# A.net
KiCad netlist of a schematic drawn in Altium Designer
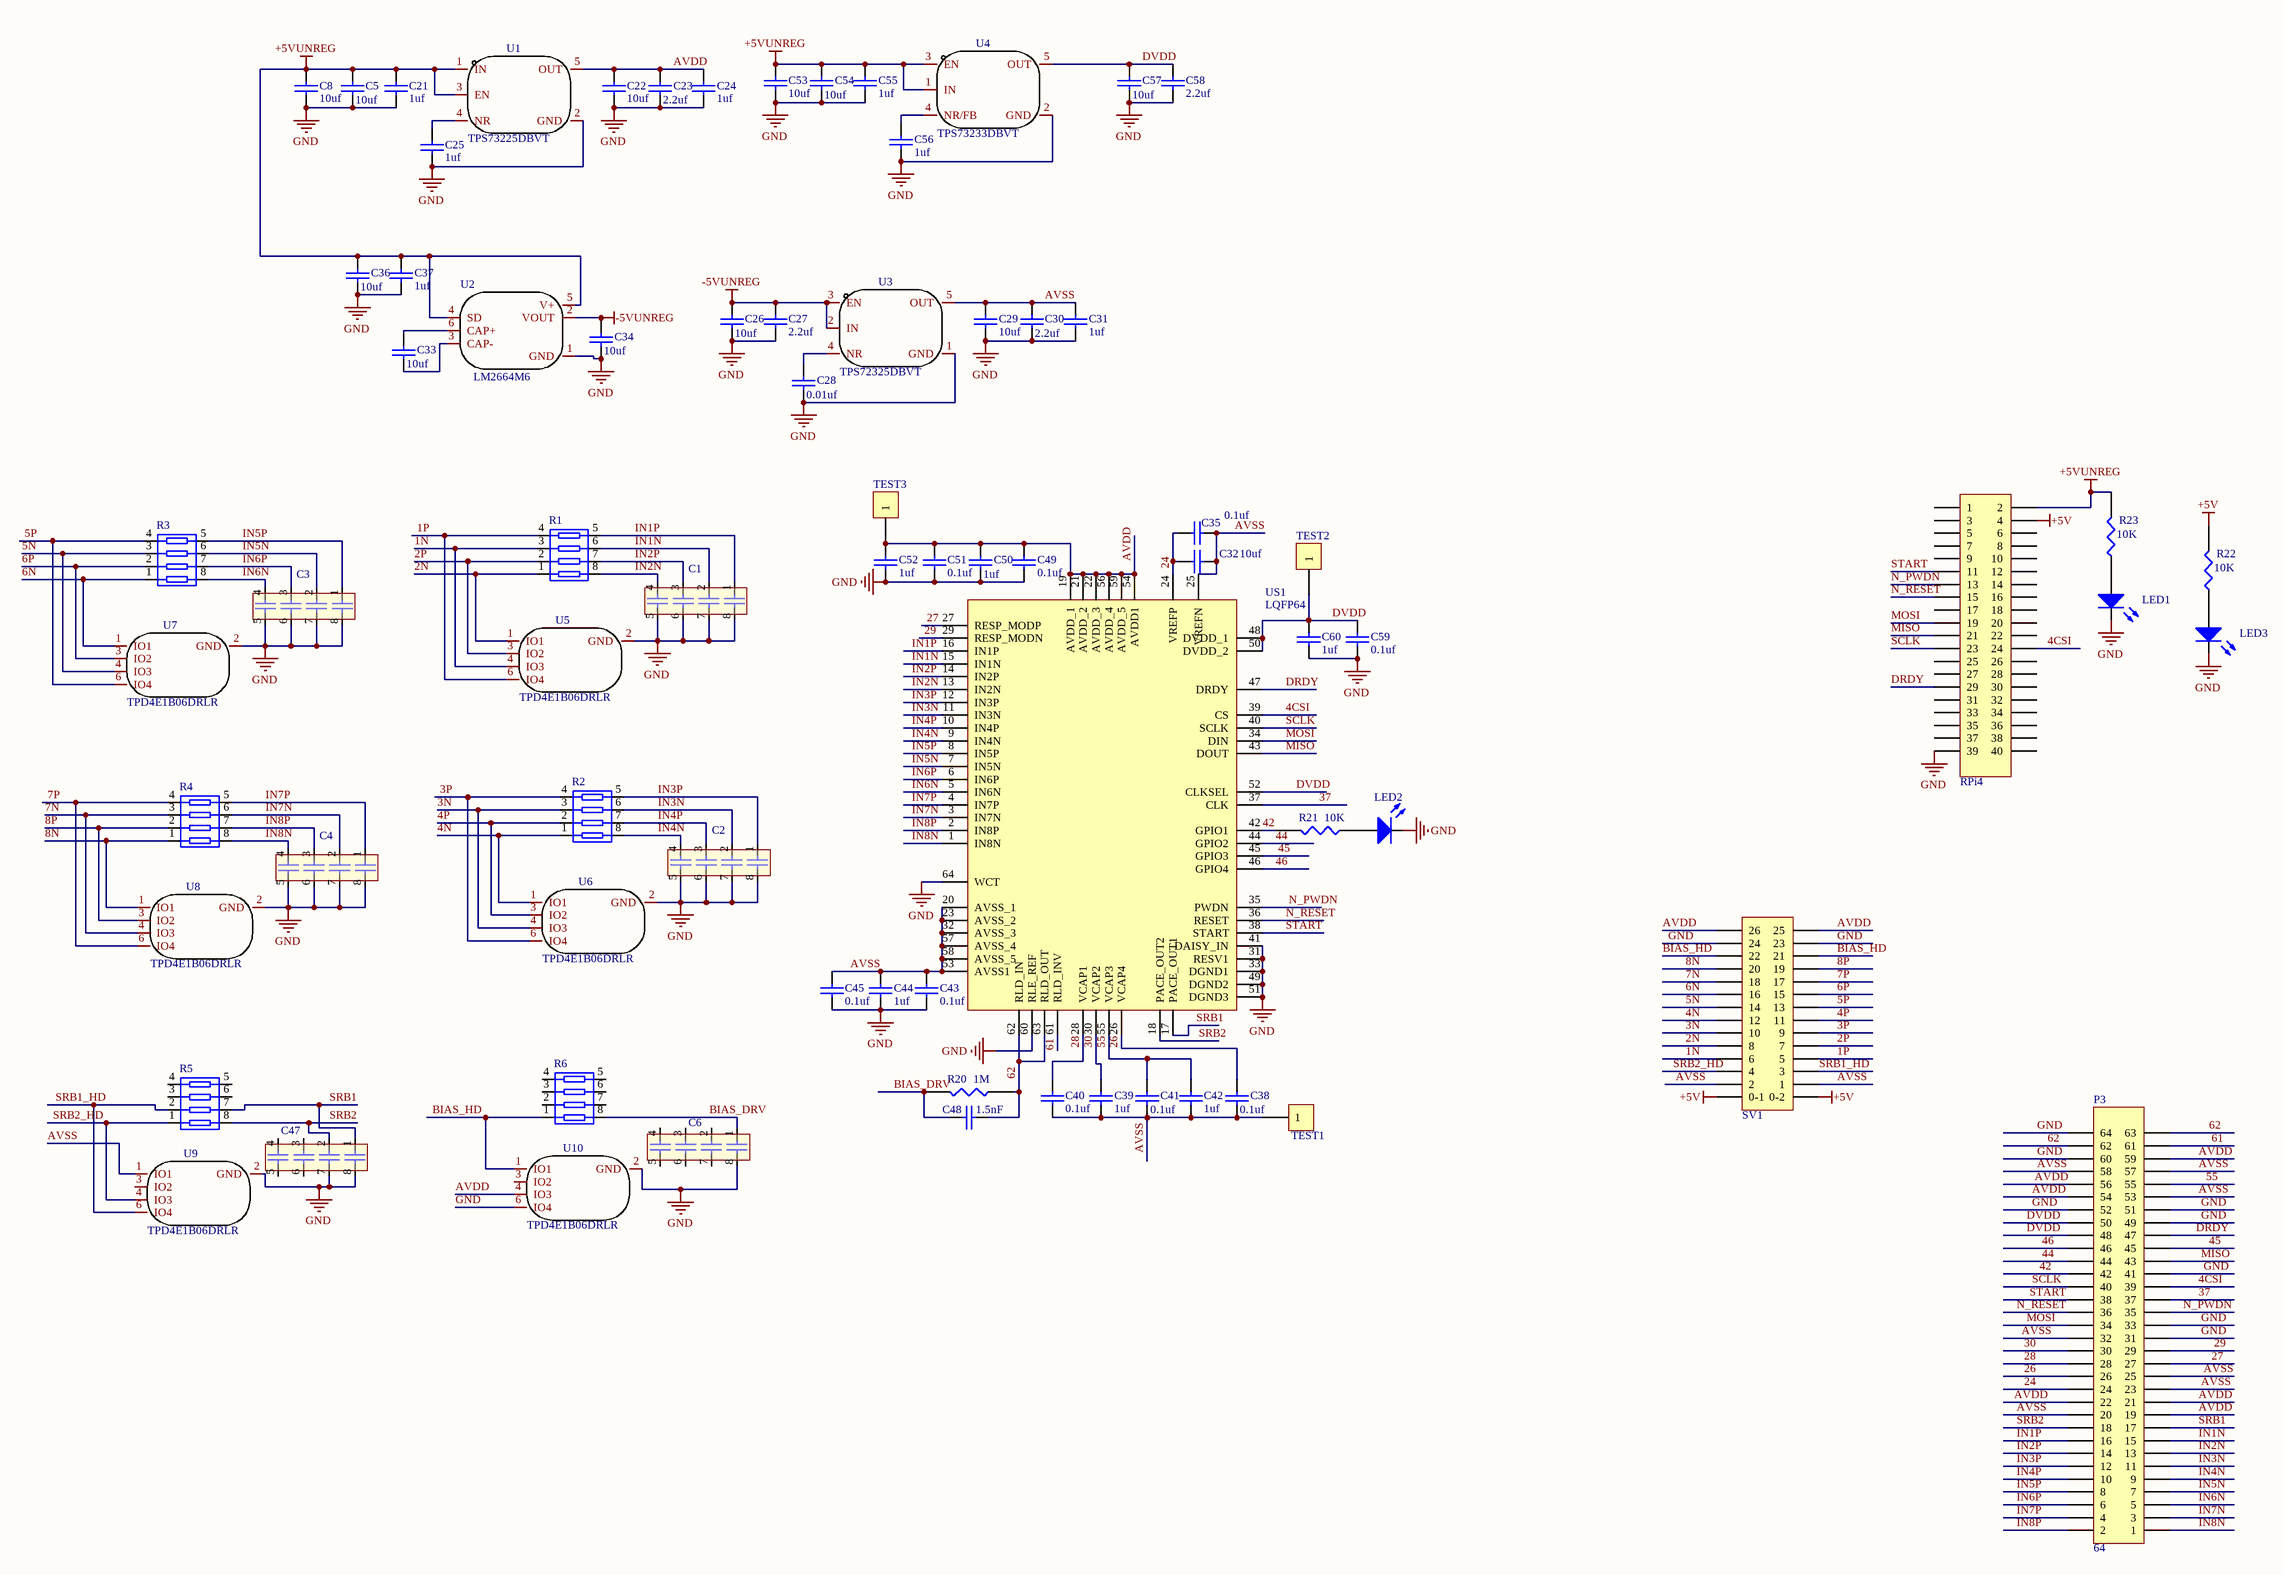
[diagram p0: A.SchDoc]

(export (version "E")
  (design (tool "Eeschema 10.0.6"))
  (components
    (comp (ref "C1") (value "~") (footprint "0805 array") (libsource (lib "") (part "8P4R_1")))
    (comp (ref "C2") (value "~") (footprint "0805 array") (libsource (lib "") (part "8P4R_1")))
    (comp (ref "C3") (value "~") (footprint "0805 array") (libsource (lib "") (part "8P4R_1")))
    (comp (ref "C4") (value "~") (footprint "0805 array") (libsource (lib "") (part "8P4R_1")))
    (comp (ref "C5")
      (value "10uf")
      (footprint "0805")
      (description "Capacitor")
      (libsource (lib "*") (part "CAP"))
    )
    (comp (ref "C6") (value "~") (footprint "0805 array") (libsource (lib "") (part "8P4R_1")))
    (comp (ref "C8")
      (value "10uf")
      (footprint "0805")
      (description "Capacitor")
      (libsource (lib "*") (part "CAP"))
    )
    (comp (ref "C21")
      (value "1uf")
      (footprint "0805")
      (description "Capacitor")
      (libsource (lib "*") (part "CAP"))
    )
    (comp (ref "C22")
      (value "10uf")
      (footprint "0805")
      (description "Capacitor")
      (libsource (lib "*") (part "CAP"))
    )
    (comp (ref "C23")
      (value "2.2uf")
      (footprint "0805")
      (description "Capacitor")
      (libsource (lib "*") (part "CAP"))
    )
    (comp (ref "C24")
      (value "1uf")
      (footprint "0805")
      (description "Capacitor")
      (libsource (lib "*") (part "CAP"))
    )
    (comp (ref "C25")
      (value "1uf")
      (footprint "0805")
      (description "Capacitor")
      (libsource (lib "*") (part "CAP"))
    )
    (comp (ref "C26")
      (value "10uf")
      (footprint "0805")
      (description "Capacitor")
      (libsource (lib "*") (part "CAP"))
    )
    (comp (ref "C27")
      (value "2.2uf")
      (footprint "0805")
      (description "Capacitor")
      (libsource (lib "*") (part "CAP"))
    )
    (comp (ref "C28")
      (value "0.01uf")
      (footprint "0805")
      (description "Capacitor")
      (libsource (lib "*") (part "CAP"))
    )
    (comp (ref "C29")
      (value "10uf")
      (footprint "0805")
      (description "Capacitor")
      (libsource (lib "*") (part "CAP"))
    )
    (comp (ref "C30")
      (value "2.2uf")
      (footprint "0805")
      (description "Capacitor")
      (libsource (lib "*") (part "CAP"))
    )
    (comp (ref "C31")
      (value "1uf")
      (footprint "0805")
      (description "Capacitor")
      (libsource (lib "*") (part "CAP"))
    )
    (comp (ref "C32")
      (value "10uf")
      (footprint "0805")
      (description "Capacitor")
      (libsource (lib "*") (part "CAP"))
    )
    (comp (ref "C33")
      (value "10uf")
      (footprint "0805")
      (description "Capacitor")
      (libsource (lib "*") (part "CAP"))
    )
    (comp (ref "C34")
      (value "10uf")
      (footprint "0805")
      (description "Capacitor")
      (libsource (lib "*") (part "CAP"))
    )
    (comp (ref "C35")
      (value "0.1uf")
      (footprint "0805")
      (description "Capacitor")
      (libsource (lib "*") (part "CAP"))
    )
    (comp (ref "C36")
      (value "10uf")
      (footprint "0805")
      (description "Capacitor")
      (libsource (lib "*") (part "CAP"))
    )
    (comp (ref "C37")
      (value "1uf")
      (footprint "0805")
      (description "Capacitor")
      (libsource (lib "*") (part "CAP"))
    )
    (comp (ref "C38")
      (value "0.1uf")
      (footprint "0805")
      (description "Capacitor")
      (libsource (lib "*") (part "CAP"))
    )
    (comp (ref "C39")
      (value "1uf")
      (footprint "0805")
      (description "Capacitor")
      (libsource (lib "*") (part "CAP"))
    )
    (comp (ref "C40")
      (value "0.1uf")
      (footprint "0805")
      (description "Capacitor")
      (libsource (lib "*") (part "CAP"))
    )
    (comp (ref "C41")
      (value "0.1uf")
      (footprint "0805")
      (description "Capacitor")
      (libsource (lib "*") (part "CAP"))
    )
    (comp (ref "C42")
      (value "1uf")
      (footprint "0805")
      (description "Capacitor")
      (libsource (lib "*") (part "CAP"))
    )
    (comp (ref "C43")
      (value "0.1uf")
      (footprint "0805")
      (description "Capacitor")
      (libsource (lib "*") (part "CAP"))
    )
    (comp (ref "C44")
      (value "1uf")
      (footprint "0805")
      (description "Capacitor")
      (libsource (lib "*") (part "CAP"))
    )
    (comp (ref "C45")
      (value "0.1uf")
      (footprint "0805")
      (description "Capacitor")
      (libsource (lib "*") (part "CAP"))
    )
    (comp (ref "C47") (value "~") (footprint "0805 array") (libsource (lib "") (part "8P4R_1")))
    (comp (ref "C48")
      (value "1.5nF")
      (footprint "0805")
      (description "Capacitor")
      (libsource (lib "*") (part "CAP"))
    )
    (comp (ref "C49")
      (value "0.1uf")
      (footprint "0805")
      (description "Capacitor")
      (libsource (lib "*") (part "CAP"))
    )
    (comp (ref "C50")
      (value "1uf")
      (footprint "0805")
      (description "Capacitor")
      (libsource (lib "*") (part "CAP"))
    )
    (comp (ref "C51")
      (value "0.1uf")
      (footprint "0805")
      (description "Capacitor")
      (libsource (lib "*") (part "CAP"))
    )
    (comp (ref "C52")
      (value "1uf")
      (footprint "0805")
      (description "Capacitor")
      (libsource (lib "*") (part "CAP"))
    )
    (comp (ref "C53")
      (value "10uf")
      (footprint "0805")
      (description "Capacitor")
      (libsource (lib "*") (part "CAP"))
    )
    (comp (ref "C54")
      (value "10uf")
      (footprint "0805")
      (description "Capacitor")
      (libsource (lib "*") (part "CAP"))
    )
    (comp (ref "C55")
      (value "1uf")
      (footprint "0805")
      (description "Capacitor")
      (libsource (lib "*") (part "CAP"))
    )
    (comp (ref "C56")
      (value "1uf")
      (footprint "0805")
      (description "Capacitor")
      (libsource (lib "*") (part "CAP"))
    )
    (comp (ref "C57")
      (value "10uf")
      (footprint "0805")
      (description "Capacitor")
      (libsource (lib "*") (part "CAP"))
    )
    (comp (ref "C58")
      (value "2.2uf")
      (footprint "0805")
      (description "Capacitor")
      (libsource (lib "*") (part "CAP"))
    )
    (comp (ref "C59")
      (value "0.1uf")
      (footprint "0805")
      (description "Capacitor")
      (libsource (lib "*") (part "CAP"))
    )
    (comp (ref "C60")
      (value "1uf")
      (footprint "0805")
      (description "Capacitor")
      (libsource (lib "*") (part "CAP"))
    )
    (comp (ref "LED1") (value "~") (footprint "0805") (libsource (lib "schematic library") (part "LED")))
    (comp (ref "LED2") (value "~") (footprint "0805") (libsource (lib "schematic library") (part "LED")))
    (comp (ref "LED3") (value "~") (footprint "0805") (libsource (lib "schematic library") (part "LED")))
    (comp (ref "P3") (value "64") (footprint "64") (libsource (lib "1299") (part "64")))
    (comp (ref "R1") (value "~") (footprint "8P4R") (libsource (lib "schematic library") (part "8P4R")))
    (comp (ref "R2") (value "~") (footprint "8P4R") (libsource (lib "schematic library") (part "8P4R")))
    (comp (ref "R3") (value "~") (footprint "8P4R") (libsource (lib "schematic library") (part "8P4R")))
    (comp (ref "R4") (value "~") (footprint "8P4R") (libsource (lib "schematic library") (part "8P4R")))
    (comp (ref "R5") (value "~") (footprint "8P4R") (libsource (lib "schematic library") (part "8P4R")))
    (comp (ref "R6") (value "~") (footprint "8P4R") (libsource (lib "schematic library") (part "8P4R")))
    (comp (ref "R20") (value "1M") (footprint "0805") (libsource (lib "*") (part "RES1")))
    (comp (ref "R21") (value "10K") (footprint "0805") (libsource (lib "*") (part "RES1")))
    (comp (ref "R22") (value "10K") (footprint "0805") (libsource (lib "*") (part "RES1")))
    (comp (ref "R23") (value "10K") (footprint "0805") (libsource (lib "*") (part "RES1")))
    (comp (ref "RPi4") (value "RP13") (footprint "40") (libsource (lib "1299") (part "40")))
    (comp (ref "SV1") (value "SV1") (footprint "26") (libsource (lib "A") (part "26")))
    (comp (ref "TEST1")
      (value "TEST2")
      (footprint "P")
      (description "Connector")
      (libsource (lib "") (part "CON1_1"))
    )
    (comp (ref "TEST2")
      (value "TEST3")
      (footprint "P")
      (description "Connector")
      (libsource (lib "*") (part "CON1"))
    )
    (comp (ref "TEST3")
      (value "TEST4")
      (footprint "P")
      (description "Connector")
      (libsource (lib "*") (part "CON1"))
    )
    (comp (ref "U1") (value "TPS73225DBVT") (footprint "sot23-5") (libsource (lib "1299") (part "5")))
    (comp (ref "U2") (value "LM2664M6") (footprint "sot23-6") (libsource (lib "1299") (part "6")))
    (comp (ref "U3") (value "TPS72325DBVT") (footprint "sot23-5") (libsource (lib "") (part "5_2")))
    (comp (ref "U4") (value "TPS73233DBVT") (footprint "sot23-5") (libsource (lib "") (part "5_1")))
    (comp (ref "U5") (value "TPD4E1B06DRLR") (footprint "sot563") (libsource (lib "1299") (part "6+")))
    (comp (ref "U6") (value "TPD4E1B06DRLR") (footprint "sot563") (libsource (lib "1299") (part "6+")))
    (comp (ref "U7") (value "TPD4E1B06DRLR") (footprint "sot563") (libsource (lib "1299") (part "6+")))
    (comp (ref "U8") (value "TPD4E1B06DRLR") (footprint "sot563") (libsource (lib "1299") (part "6+")))
    (comp (ref "U9") (value "TPD4E1B06DRLR") (footprint "sot563") (libsource (lib "1299") (part "6+")))
    (comp (ref "U10") (value "TPD4E1B06DRLR") (footprint "sot563") (libsource (lib "1299") (part "6+")))
    (comp (ref "US1") (value "LQFP64") (footprint "TQFP64") (libsource (lib "1299") (part "LQFP64")))
  )
  (nets
    (net (code "1") (name "+5V") (class "Default")
      (node (ref "R22") (pin "2") (pinfunction "2_2") (pintype "passive"))
      (node (ref "RPi4") (pin "4") (pinfunction "4_4") (pintype "passive"))
      (node (ref "SV1") (pin "0-1") (pinfunction "0-1_0-1") (pintype "passive"))
      (node (ref "SV1") (pin "0-2") (pinfunction "0-2_0-2") (pintype "passive"))
    )
    (net (code "2") (name "+5VUNREG") (class "Default")
      (node (ref "C21") (pin "1") (pinfunction "1_1") (pintype "passive"))
      (node (ref "C36") (pin "1") (pinfunction "1_1") (pintype "passive"))
      (node (ref "C37") (pin "1") (pinfunction "1_1") (pintype "passive"))
      (node (ref "C5") (pin "1") (pinfunction "1_1") (pintype "passive"))
      (node (ref "C53") (pin "1") (pinfunction "1_1") (pintype "passive"))
      (node (ref "C54") (pin "1") (pinfunction "1_1") (pintype "passive"))
      (node (ref "C55") (pin "1") (pinfunction "1_1") (pintype "passive"))
      (node (ref "C8") (pin "1") (pinfunction "1_1") (pintype "passive"))
      (node (ref "R23") (pin "2") (pinfunction "2_2") (pintype "passive"))
      (node (ref "RPi4") (pin "2") (pinfunction "2_2") (pintype "passive"))
      (node (ref "U1") (pin "1") (pinfunction "IN_1") (pintype "passive"))
      (node (ref "U1") (pin "3") (pinfunction "EN_3") (pintype "passive"))
      (node (ref "U2") (pin "4") (pinfunction "SD_4") (pintype "passive"))
      (node (ref "U2") (pin "5") (pinfunction "V+_5") (pintype "passive"))
      (node (ref "U4") (pin "1") (pinfunction "IN_1") (pintype "passive"))
      (node (ref "U4") (pin "3") (pinfunction "EN_3") (pintype "passive"))
    )
    (net (code "3") (name "-5VUNREG") (class "Default")
      (node (ref "C26") (pin "1") (pinfunction "1_1") (pintype "passive"))
      (node (ref "C27") (pin "1") (pinfunction "1_1") (pintype "passive"))
      (node (ref "C34") (pin "1") (pinfunction "1_1") (pintype "passive"))
      (node (ref "U2") (pin "2") (pinfunction "VOUT_2") (pintype "passive"))
      (node (ref "U3") (pin "2") (pinfunction "IN_2") (pintype "passive"))
      (node (ref "U3") (pin "3") (pinfunction "EN_3") (pintype "passive"))
    )
    (net (code "4") (name "/1N") (class "Default")
      (node (ref "R1") (pin "3") (pinfunction "3_3") (pintype "passive"))
      (node (ref "SV1") (pin "6") (pinfunction "6_6") (pintype "passive"))
      (node (ref "U5") (pin "4") (pinfunction "IO3_4") (pintype "passive"))
    )
    (net (code "5") (name "/1P") (class "Default")
      (node (ref "R1") (pin "4") (pinfunction "4_4") (pintype "passive"))
      (node (ref "SV1") (pin "5") (pinfunction "5_5") (pintype "passive"))
      (node (ref "U5") (pin "6") (pinfunction "IO4_6") (pintype "passive"))
    )
    (net (code "6") (name "/2N") (class "Default")
      (node (ref "R1") (pin "1") (pinfunction "1_1") (pintype "passive"))
      (node (ref "SV1") (pin "8") (pinfunction "8_8") (pintype "passive"))
      (node (ref "U5") (pin "1") (pinfunction "IO1_1") (pintype "passive"))
    )
    (net (code "7") (name "/2P") (class "Default")
      (node (ref "R1") (pin "2") (pinfunction "2_2") (pintype "passive"))
      (node (ref "SV1") (pin "7") (pinfunction "7_7") (pintype "passive"))
      (node (ref "U5") (pin "3") (pinfunction "IO2_3") (pintype "passive"))
    )
    (net (code "8") (name "/3N") (class "Default")
      (node (ref "R2") (pin "3") (pinfunction "3_3") (pintype "passive"))
      (node (ref "SV1") (pin "10") (pinfunction "10_10") (pintype "passive"))
      (node (ref "U6") (pin "4") (pinfunction "IO3_4") (pintype "passive"))
    )
    (net (code "9") (name "/3P") (class "Default")
      (node (ref "R2") (pin "4") (pinfunction "4_4") (pintype "passive"))
      (node (ref "SV1") (pin "9") (pinfunction "9_9") (pintype "passive"))
      (node (ref "U6") (pin "6") (pinfunction "IO4_6") (pintype "passive"))
    )
    (net (code "10") (name "/4CSI") (class "Default")
      (node (ref "P3") (pin "39") (pinfunction "39_39") (pintype "passive"))
      (node (ref "RPi4") (pin "24") (pinfunction "24_24") (pintype "passive"))
      (node (ref "US1") (pin "39") (pinfunction "CS_39") (pintype "passive"))
    )
    (net (code "11") (name "/4N") (class "Default")
      (node (ref "R2") (pin "1") (pinfunction "1_1") (pintype "passive"))
      (node (ref "SV1") (pin "12") (pinfunction "12_12") (pintype "passive"))
      (node (ref "U6") (pin "1") (pinfunction "IO1_1") (pintype "passive"))
    )
    (net (code "12") (name "/4P") (class "Default")
      (node (ref "R2") (pin "2") (pinfunction "2_2") (pintype "passive"))
      (node (ref "SV1") (pin "11") (pinfunction "11_11") (pintype "passive"))
      (node (ref "U6") (pin "3") (pinfunction "IO2_3") (pintype "passive"))
    )
    (net (code "13") (name "/5N") (class "Default")
      (node (ref "R3") (pin "3") (pinfunction "3_3") (pintype "passive"))
      (node (ref "SV1") (pin "14") (pinfunction "14_14") (pintype "passive"))
      (node (ref "U7") (pin "4") (pinfunction "IO3_4") (pintype "passive"))
    )
    (net (code "14") (name "/5P") (class "Default")
      (node (ref "R3") (pin "4") (pinfunction "4_4") (pintype "passive"))
      (node (ref "SV1") (pin "13") (pinfunction "13_13") (pintype "passive"))
      (node (ref "U7") (pin "6") (pinfunction "IO4_6") (pintype "passive"))
    )
    (net (code "15") (name "/6N") (class "Default")
      (node (ref "R3") (pin "1") (pinfunction "1_1") (pintype "passive"))
      (node (ref "SV1") (pin "16") (pinfunction "16_16") (pintype "passive"))
      (node (ref "U7") (pin "1") (pinfunction "IO1_1") (pintype "passive"))
    )
    (net (code "16") (name "/6P") (class "Default")
      (node (ref "R3") (pin "2") (pinfunction "2_2") (pintype "passive"))
      (node (ref "SV1") (pin "15") (pinfunction "15_15") (pintype "passive"))
      (node (ref "U7") (pin "3") (pinfunction "IO2_3") (pintype "passive"))
    )
    (net (code "17") (name "/7N") (class "Default")
      (node (ref "R4") (pin "3") (pinfunction "3_3") (pintype "passive"))
      (node (ref "SV1") (pin "18") (pinfunction "18_18") (pintype "passive"))
      (node (ref "U8") (pin "4") (pinfunction "IO3_4") (pintype "passive"))
    )
    (net (code "18") (name "/7P") (class "Default")
      (node (ref "R4") (pin "4") (pinfunction "4_4") (pintype "passive"))
      (node (ref "SV1") (pin "17") (pinfunction "17_17") (pintype "passive"))
      (node (ref "U8") (pin "6") (pinfunction "IO4_6") (pintype "passive"))
    )
    (net (code "19") (name "/8N") (class "Default")
      (node (ref "R4") (pin "1") (pinfunction "1_1") (pintype "passive"))
      (node (ref "SV1") (pin "20") (pinfunction "20_20") (pintype "passive"))
      (node (ref "U8") (pin "1") (pinfunction "IO1_1") (pintype "passive"))
    )
    (net (code "20") (name "/8P") (class "Default")
      (node (ref "R4") (pin "2") (pinfunction "2_2") (pintype "passive"))
      (node (ref "SV1") (pin "19") (pinfunction "19_19") (pintype "passive"))
      (node (ref "U8") (pin "3") (pinfunction "IO2_3") (pintype "passive"))
    )
    (net (code "21") (name "/24") (class "Default")
      (node (ref "C32") (pin "1") (pinfunction "1_1") (pintype "passive"))
      (node (ref "C35") (pin "2") (pinfunction "2_2") (pintype "passive"))
      (node (ref "P3") (pin "24") (pinfunction "24_24") (pintype "passive"))
      (node (ref "US1") (pin "24") (pinfunction "VREFP_24") (pintype "passive"))
    )
    (net (code "22") (name "/26") (class "Default")
      (node (ref "C38") (pin "1") (pinfunction "1_1") (pintype "passive"))
      (node (ref "P3") (pin "26") (pinfunction "26_26") (pintype "passive"))
      (node (ref "US1") (pin "26") (pinfunction "VCAP4_26") (pintype "passive"))
    )
    (net (code "23") (name "/27") (class "Default")
      (node (ref "P3") (pin "27") (pinfunction "27_27") (pintype "passive"))
      (node (ref "US1") (pin "27") (pinfunction "RESP_MODP_27") (pintype "passive"))
    )
    (net (code "24") (name "/28") (class "Default")
      (node (ref "C40") (pin "1") (pinfunction "1_1") (pintype "passive"))
      (node (ref "P3") (pin "28") (pinfunction "28_28") (pintype "passive"))
      (node (ref "US1") (pin "28") (pinfunction "VCAP1_28") (pintype "passive"))
    )
    (net (code "25") (name "/29") (class "Default")
      (node (ref "P3") (pin "29") (pinfunction "29_29") (pintype "passive"))
      (node (ref "US1") (pin "29") (pinfunction "RESP_MODN_29") (pintype "passive"))
    )
    (net (code "26") (name "/30") (class "Default")
      (node (ref "C39") (pin "1") (pinfunction "1_1") (pintype "passive"))
      (node (ref "P3") (pin "30") (pinfunction "30_30") (pintype "passive"))
      (node (ref "US1") (pin "30") (pinfunction "VCAP2_30") (pintype "passive"))
    )
    (net (code "27") (name "/37") (class "Default")
      (node (ref "P3") (pin "37") (pinfunction "37_37") (pintype "passive"))
      (node (ref "US1") (pin "37") (pinfunction "CLK_37") (pintype "passive"))
    )
    (net (code "28") (name "/42") (class "Default")
      (node (ref "P3") (pin "42") (pinfunction "42_42") (pintype "passive"))
      (node (ref "R21") (pin "2") (pinfunction "2_2") (pintype "passive"))
      (node (ref "US1") (pin "42") (pinfunction "GPIO1_42") (pintype "passive"))
    )
    (net (code "29") (name "/44") (class "Default")
      (node (ref "P3") (pin "44") (pinfunction "44_44") (pintype "passive"))
      (node (ref "US1") (pin "44") (pinfunction "GPIO2_44") (pintype "passive"))
    )
    (net (code "30") (name "/45") (class "Default")
      (node (ref "P3") (pin "45") (pinfunction "45_45") (pintype "passive"))
      (node (ref "US1") (pin "45") (pinfunction "GPIO3_45") (pintype "passive"))
    )
    (net (code "31") (name "/46") (class "Default")
      (node (ref "P3") (pin "46") (pinfunction "46_46") (pintype "passive"))
      (node (ref "US1") (pin "46") (pinfunction "GPIO4_46") (pintype "passive"))
    )
    (net (code "32") (name "/55") (class "Default")
      (node (ref "C41") (pin "1") (pinfunction "1_1") (pintype "passive"))
      (node (ref "C42") (pin "1") (pinfunction "1_1") (pintype "passive"))
      (node (ref "P3") (pin "55") (pinfunction "55_55") (pintype "passive"))
      (node (ref "US1") (pin "55") (pinfunction "VCAP3_55") (pintype "passive"))
    )
    (net (code "33") (name "/61") (class "Default")
      (node (ref "P3") (pin "61") (pinfunction "61_61") (pintype "passive"))
      (node (ref "US1") (pin "61") (pinfunction "RLD_INV_61") (pintype "passive"))
    )
    (net (code "34") (name "/62") (class "Default")
      (node (ref "C48") (pin "2") (pinfunction "2_2") (pintype "passive"))
      (node (ref "P3") (pin "62") (pinfunction "62_62") (pintype "passive"))
      (node (ref "P3") (pin "63") (pinfunction "63_63") (pintype "passive"))
      (node (ref "R20") (pin "1") (pinfunction "1_1") (pintype "passive"))
      (node (ref "US1") (pin "62") (pinfunction "RLD_IN_62") (pintype "passive"))
      (node (ref "US1") (pin "63") (pinfunction "RLD_OUT_63") (pintype "passive"))
    )
    (net (code "35") (name "/AVDD") (class "Default")
      (node (ref "C22") (pin "1") (pinfunction "1_1") (pintype "passive"))
      (node (ref "C23") (pin "1") (pinfunction "1_1") (pintype "passive"))
      (node (ref "C24") (pin "1") (pinfunction "1_1") (pintype "passive"))
      (node (ref "C49") (pin "1") (pinfunction "1_1") (pintype "passive"))
      (node (ref "C50") (pin "1") (pinfunction "1_1") (pintype "passive"))
      (node (ref "C51") (pin "1") (pinfunction "1_1") (pintype "passive"))
      (node (ref "C52") (pin "1") (pinfunction "1_1") (pintype "passive"))
      (node (ref "P3") (pin "19") (pinfunction "19_19") (pintype "passive"))
      (node (ref "P3") (pin "21") (pinfunction "21_21") (pintype "passive"))
      (node (ref "P3") (pin "22") (pinfunction "22_22") (pintype "passive"))
      (node (ref "P3") (pin "54") (pinfunction "54_54") (pintype "passive"))
      (node (ref "P3") (pin "56") (pinfunction "56_56") (pintype "passive"))
      (node (ref "P3") (pin "59") (pinfunction "59_59") (pintype "passive"))
      (node (ref "SV1") (pin "25") (pinfunction "25_25") (pintype "passive"))
      (node (ref "SV1") (pin "26") (pinfunction "26_26") (pintype "passive"))
      (node (ref "TEST3") (pin "1") (pinfunction "1_1") (pintype "passive"))
      (node (ref "U1") (pin "5") (pinfunction "OUT_5") (pintype "passive"))
      (node (ref "U10") (pin "4") (pinfunction "IO3_4") (pintype "passive"))
      (node (ref "US1") (pin "19") (pinfunction "AVDD_1_19") (pintype "passive"))
      (node (ref "US1") (pin "21") (pinfunction "AVDD_2_21") (pintype "passive"))
      (node (ref "US1") (pin "22") (pinfunction "AVDD_3_22") (pintype "passive"))
      (node (ref "US1") (pin "54") (pinfunction "AVDD1_54") (pintype "passive"))
      (node (ref "US1") (pin "56") (pinfunction "AVDD_4_56") (pintype "passive"))
      (node (ref "US1") (pin "59") (pinfunction "AVDD_5_59") (pintype "passive"))
    )
    (net (code "36") (name "/AVSS") (class "Default")
      (node (ref "C29") (pin "1") (pinfunction "1_1") (pintype "passive"))
      (node (ref "C30") (pin "1") (pinfunction "1_1") (pintype "passive"))
      (node (ref "C31") (pin "1") (pinfunction "1_1") (pintype "passive"))
      (node (ref "C32") (pin "2") (pinfunction "2_2") (pintype "passive"))
      (node (ref "C35") (pin "1") (pinfunction "1_1") (pintype "passive"))
      (node (ref "C38") (pin "2") (pinfunction "2_2") (pintype "passive"))
      (node (ref "C39") (pin "2") (pinfunction "2_2") (pintype "passive"))
      (node (ref "C40") (pin "2") (pinfunction "2_2") (pintype "passive"))
      (node (ref "C41") (pin "2") (pinfunction "2_2") (pintype "passive"))
      (node (ref "C42") (pin "2") (pinfunction "2_2") (pintype "passive"))
      (node (ref "C43") (pin "1") (pinfunction "1_1") (pintype "passive"))
      (node (ref "C44") (pin "1") (pinfunction "1_1") (pintype "passive"))
      (node (ref "C45") (pin "1") (pinfunction "1_1") (pintype "passive"))
      (node (ref "P3") (pin "20") (pinfunction "20_20") (pintype "passive"))
      (node (ref "P3") (pin "23") (pinfunction "23_23") (pintype "passive"))
      (node (ref "P3") (pin "25") (pinfunction "25_25") (pintype "passive"))
      (node (ref "P3") (pin "32") (pinfunction "32_32") (pintype "passive"))
      (node (ref "P3") (pin "53") (pinfunction "53_53") (pintype "passive"))
      (node (ref "P3") (pin "57") (pinfunction "57_57") (pintype "passive"))
      (node (ref "P3") (pin "58") (pinfunction "58_58") (pintype "passive"))
      (node (ref "SV1") (pin "1") (pinfunction "1_1") (pintype "passive"))
      (node (ref "SV1") (pin "2") (pinfunction "2_2") (pintype "passive"))
      (node (ref "TEST1") (pin "1") (pinfunction "1_1") (pintype "passive"))
      (node (ref "U3") (pin "5") (pinfunction "OUT_5") (pintype "passive"))
      (node (ref "U9") (pin "1") (pinfunction "IO1_1") (pintype "passive"))
      (node (ref "US1") (pin "20") (pinfunction "AVSS_1_20") (pintype "passive"))
      (node (ref "US1") (pin "23") (pinfunction "AVSS_2_23") (pintype "passive"))
      (node (ref "US1") (pin "25") (pinfunction "VREFN_25") (pintype "passive"))
      (node (ref "US1") (pin "32") (pinfunction "AVSS_3_32") (pintype "passive"))
      (node (ref "US1") (pin "53") (pinfunction "AVSS1_53") (pintype "passive"))
      (node (ref "US1") (pin "57") (pinfunction "AVSS_4_57") (pintype "passive"))
      (node (ref "US1") (pin "58") (pinfunction "AVSS_5_58") (pintype "passive"))
    )
    (net (code "37") (name "/BIAS_DRV") (class "Default")
      (node (ref "C48") (pin "1") (pinfunction "1_1") (pintype "passive"))
      (node (ref "C6") (pin "1") (pinfunction "1_1") (pintype "passive"))
      (node (ref "R20") (pin "2") (pinfunction "2_2") (pintype "passive"))
      (node (ref "R6") (pin "8") (pinfunction "8_8") (pintype "passive"))
    )
    (net (code "38") (name "/BIAS_HD") (class "Default")
      (node (ref "R6") (pin "1") (pinfunction "1_1") (pintype "passive"))
      (node (ref "SV1") (pin "21") (pinfunction "21_21") (pintype "passive"))
      (node (ref "SV1") (pin "22") (pinfunction "22_22") (pintype "passive"))
      (node (ref "U10") (pin "1") (pinfunction "IO1_1") (pintype "passive"))
    )
    (net (code "39") (name "/DRDY") (class "Default")
      (node (ref "P3") (pin "47") (pinfunction "47_47") (pintype "passive"))
      (node (ref "RPi4") (pin "29") (pinfunction "29_29") (pintype "passive"))
      (node (ref "US1") (pin "47") (pinfunction "DRDY_47") (pintype "passive"))
    )
    (net (code "40") (name "/DVDD") (class "Default")
      (node (ref "C57") (pin "1") (pinfunction "1_1") (pintype "passive"))
      (node (ref "C58") (pin "1") (pinfunction "1_1") (pintype "passive"))
      (node (ref "C59") (pin "2") (pinfunction "2_2") (pintype "passive"))
      (node (ref "C60") (pin "1") (pinfunction "1_1") (pintype "passive"))
      (node (ref "P3") (pin "48") (pinfunction "48_48") (pintype "passive"))
      (node (ref "P3") (pin "50") (pinfunction "50_50") (pintype "passive"))
      (node (ref "TEST2") (pin "1") (pinfunction "1_1") (pintype "passive"))
      (node (ref "U4") (pin "5") (pinfunction "OUT_5") (pintype "passive"))
      (node (ref "US1") (pin "48") (pinfunction "DVDD_1_48") (pintype "passive"))
      (node (ref "US1") (pin "50") (pinfunction "DVDD_2_50") (pintype "passive"))
      (node (ref "US1") (pin "52") (pinfunction "CLKSEL_52") (pintype "passive"))
    )
    (net (code "41") (name "/IN1N") (class "Default")
      (node (ref "C1") (pin "2") (pinfunction "2_2") (pintype "passive"))
      (node (ref "P3") (pin "15") (pinfunction "15_15") (pintype "passive"))
      (node (ref "R1") (pin "6") (pinfunction "6_6") (pintype "passive"))
      (node (ref "US1") (pin "15") (pinfunction "IN1N_15") (pintype "passive"))
    )
    (net (code "42") (name "/IN1P") (class "Default")
      (node (ref "C1") (pin "1") (pinfunction "1_1") (pintype "passive"))
      (node (ref "P3") (pin "16") (pinfunction "16_16") (pintype "passive"))
      (node (ref "R1") (pin "5") (pinfunction "5_5") (pintype "passive"))
      (node (ref "US1") (pin "16") (pinfunction "IN1P_16") (pintype "passive"))
    )
    (net (code "43") (name "/IN2N") (class "Default")
      (node (ref "C1") (pin "4") (pinfunction "4_4") (pintype "passive"))
      (node (ref "P3") (pin "13") (pinfunction "13_13") (pintype "passive"))
      (node (ref "R1") (pin "8") (pinfunction "8_8") (pintype "passive"))
      (node (ref "US1") (pin "13") (pinfunction "IN2N_13") (pintype "passive"))
    )
    (net (code "44") (name "/IN2P") (class "Default")
      (node (ref "C1") (pin "3") (pinfunction "3_3") (pintype "passive"))
      (node (ref "P3") (pin "14") (pinfunction "14_14") (pintype "passive"))
      (node (ref "R1") (pin "7") (pinfunction "7_7") (pintype "passive"))
      (node (ref "US1") (pin "14") (pinfunction "IN2P_14") (pintype "passive"))
    )
    (net (code "45") (name "/IN3N") (class "Default")
      (node (ref "C2") (pin "2") (pinfunction "2_2") (pintype "passive"))
      (node (ref "P3") (pin "11") (pinfunction "11_11") (pintype "passive"))
      (node (ref "R2") (pin "6") (pinfunction "6_6") (pintype "passive"))
      (node (ref "US1") (pin "11") (pinfunction "IN3N_11") (pintype "passive"))
    )
    (net (code "46") (name "/IN3P") (class "Default")
      (node (ref "C2") (pin "1") (pinfunction "1_1") (pintype "passive"))
      (node (ref "P3") (pin "12") (pinfunction "12_12") (pintype "passive"))
      (node (ref "R2") (pin "5") (pinfunction "5_5") (pintype "passive"))
      (node (ref "US1") (pin "12") (pinfunction "IN3P_12") (pintype "passive"))
    )
    (net (code "47") (name "/IN4N") (class "Default")
      (node (ref "C2") (pin "4") (pinfunction "4_4") (pintype "passive"))
      (node (ref "P3") (pin "9") (pinfunction "9_9") (pintype "passive"))
      (node (ref "R2") (pin "8") (pinfunction "8_8") (pintype "passive"))
      (node (ref "US1") (pin "9") (pinfunction "IN4N_9") (pintype "passive"))
    )
    (net (code "48") (name "/IN4P") (class "Default")
      (node (ref "C2") (pin "3") (pinfunction "3_3") (pintype "passive"))
      (node (ref "P3") (pin "10") (pinfunction "10_10") (pintype "passive"))
      (node (ref "R2") (pin "7") (pinfunction "7_7") (pintype "passive"))
      (node (ref "US1") (pin "10") (pinfunction "IN4P_10") (pintype "passive"))
    )
    (net (code "49") (name "/IN5N") (class "Default")
      (node (ref "C3") (pin "2") (pinfunction "2_2") (pintype "passive"))
      (node (ref "P3") (pin "7") (pinfunction "7_7") (pintype "passive"))
      (node (ref "R3") (pin "6") (pinfunction "6_6") (pintype "passive"))
      (node (ref "US1") (pin "7") (pinfunction "IN5N_7") (pintype "passive"))
    )
    (net (code "50") (name "/IN5P") (class "Default")
      (node (ref "C3") (pin "1") (pinfunction "1_1") (pintype "passive"))
      (node (ref "P3") (pin "8") (pinfunction "8_8") (pintype "passive"))
      (node (ref "R3") (pin "5") (pinfunction "5_5") (pintype "passive"))
      (node (ref "US1") (pin "8") (pinfunction "IN5P_8") (pintype "passive"))
    )
    (net (code "51") (name "/IN6N") (class "Default")
      (node (ref "C3") (pin "4") (pinfunction "4_4") (pintype "passive"))
      (node (ref "P3") (pin "5") (pinfunction "5_5") (pintype "passive"))
      (node (ref "R3") (pin "8") (pinfunction "8_8") (pintype "passive"))
      (node (ref "US1") (pin "5") (pinfunction "IN6N_5") (pintype "passive"))
    )
    (net (code "52") (name "/IN6P") (class "Default")
      (node (ref "C3") (pin "3") (pinfunction "3_3") (pintype "passive"))
      (node (ref "P3") (pin "6") (pinfunction "6_6") (pintype "passive"))
      (node (ref "R3") (pin "7") (pinfunction "7_7") (pintype "passive"))
      (node (ref "US1") (pin "6") (pinfunction "IN6P_6") (pintype "passive"))
    )
    (net (code "53") (name "/IN7N") (class "Default")
      (node (ref "C4") (pin "2") (pinfunction "2_2") (pintype "passive"))
      (node (ref "P3") (pin "3") (pinfunction "3_3") (pintype "passive"))
      (node (ref "R4") (pin "6") (pinfunction "6_6") (pintype "passive"))
      (node (ref "US1") (pin "3") (pinfunction "IN7N_3") (pintype "passive"))
    )
    (net (code "54") (name "/IN7P") (class "Default")
      (node (ref "C4") (pin "1") (pinfunction "1_1") (pintype "passive"))
      (node (ref "P3") (pin "4") (pinfunction "4_4") (pintype "passive"))
      (node (ref "R4") (pin "5") (pinfunction "5_5") (pintype "passive"))
      (node (ref "US1") (pin "4") (pinfunction "IN7P_4") (pintype "passive"))
    )
    (net (code "55") (name "/IN8N") (class "Default")
      (node (ref "C4") (pin "4") (pinfunction "4_4") (pintype "passive"))
      (node (ref "P3") (pin "1") (pinfunction "1_1") (pintype "passive"))
      (node (ref "R4") (pin "8") (pinfunction "8_8") (pintype "passive"))
      (node (ref "US1") (pin "1") (pinfunction "IN8N_1") (pintype "passive"))
    )
    (net (code "56") (name "/IN8P") (class "Default")
      (node (ref "C4") (pin "3") (pinfunction "3_3") (pintype "passive"))
      (node (ref "P3") (pin "2") (pinfunction "2_2") (pintype "passive"))
      (node (ref "R4") (pin "7") (pinfunction "7_7") (pintype "passive"))
      (node (ref "US1") (pin "2") (pinfunction "IN8P_2") (pintype "passive"))
    )
    (net (code "57") (name "/MISO") (class "Default")
      (node (ref "P3") (pin "43") (pinfunction "43_43") (pintype "passive"))
      (node (ref "RPi4") (pin "21") (pinfunction "21_21") (pintype "passive"))
      (node (ref "US1") (pin "43") (pinfunction "DOUT_43") (pintype "passive"))
    )
    (net (code "58") (name "/MOSI") (class "Default")
      (node (ref "P3") (pin "34") (pinfunction "34_34") (pintype "passive"))
      (node (ref "RPi4") (pin "19") (pinfunction "19_19") (pintype "passive"))
      (node (ref "US1") (pin "34") (pinfunction "DIN_34") (pintype "passive"))
    )
    (net (code "59") (name "/N_PWDN") (class "Default")
      (node (ref "P3") (pin "35") (pinfunction "35_35") (pintype "passive"))
      (node (ref "RPi4") (pin "13") (pinfunction "13_13") (pintype "passive"))
      (node (ref "US1") (pin "35") (pinfunction "PWDN_35") (pintype "passive"))
    )
    (net (code "60") (name "/N_RESET") (class "Default")
      (node (ref "P3") (pin "36") (pinfunction "36_36") (pintype "passive"))
      (node (ref "RPi4") (pin "15") (pinfunction "15_15") (pintype "passive"))
      (node (ref "US1") (pin "36") (pinfunction "RESET_36") (pintype "passive"))
    )
    (net (code "61") (name "/SCLK") (class "Default")
      (node (ref "P3") (pin "40") (pinfunction "40_40") (pintype "passive"))
      (node (ref "RPi4") (pin "23") (pinfunction "23_23") (pintype "passive"))
      (node (ref "US1") (pin "40") (pinfunction "SCLK_40") (pintype "passive"))
    )
    (net (code "62") (name "/SRB1") (class "Default")
      (node (ref "C47") (pin "1") (pinfunction "1_1") (pintype "passive"))
      (node (ref "P3") (pin "17") (pinfunction "17_17") (pintype "passive"))
      (node (ref "R5") (pin "7") (pinfunction "7_7") (pintype "passive"))
      (node (ref "US1") (pin "17") (pinfunction "PACE_OUT1_17") (pintype "passive"))
    )
    (net (code "63") (name "/SRB1_HD") (class "Default")
      (node (ref "R5") (pin "2") (pinfunction "2_2") (pintype "passive"))
      (node (ref "SV1") (pin "3") (pinfunction "3_3") (pintype "passive"))
      (node (ref "U9") (pin "6") (pinfunction "IO4_6") (pintype "passive"))
    )
    (net (code "64") (name "/SRB2") (class "Default")
      (node (ref "C47") (pin "2") (pinfunction "2_2") (pintype "passive"))
      (node (ref "P3") (pin "18") (pinfunction "18_18") (pintype "passive"))
      (node (ref "R5") (pin "8") (pinfunction "8_8") (pintype "passive"))
      (node (ref "US1") (pin "18") (pinfunction "PACE_OUT2_18") (pintype "passive"))
    )
    (net (code "65") (name "/SRB2_HD") (class "Default")
      (node (ref "R5") (pin "1") (pinfunction "1_1") (pintype "passive"))
      (node (ref "SV1") (pin "4") (pinfunction "4_4") (pintype "passive"))
      (node (ref "U9") (pin "4") (pinfunction "IO3_4") (pintype "passive"))
    )
    (net (code "66") (name "/START") (class "Default")
      (node (ref "P3") (pin "38") (pinfunction "38_38") (pintype "passive"))
      (node (ref "RPi4") (pin "11") (pinfunction "11_11") (pintype "passive"))
      (node (ref "US1") (pin "38") (pinfunction "START_38") (pintype "passive"))
    )
    (net (code "67") (name "GND") (class "Default")
      (node (ref "C1") (pin "5") (pinfunction "5_5") (pintype "passive"))
      (node (ref "C1") (pin "6") (pinfunction "6_6") (pintype "passive"))
      (node (ref "C1") (pin "7") (pinfunction "7_7") (pintype "passive"))
      (node (ref "C1") (pin "8") (pinfunction "8_8") (pintype "passive"))
      (node (ref "C2") (pin "5") (pinfunction "5_5") (pintype "passive"))
      (node (ref "C2") (pin "6") (pinfunction "6_6") (pintype "passive"))
      (node (ref "C2") (pin "7") (pinfunction "7_7") (pintype "passive"))
      (node (ref "C2") (pin "8") (pinfunction "8_8") (pintype "passive"))
      (node (ref "C21") (pin "2") (pinfunction "2_2") (pintype "passive"))
      (node (ref "C22") (pin "2") (pinfunction "2_2") (pintype "passive"))
      (node (ref "C23") (pin "2") (pinfunction "2_2") (pintype "passive"))
      (node (ref "C24") (pin "2") (pinfunction "2_2") (pintype "passive"))
      (node (ref "C25") (pin "2") (pinfunction "2_2") (pintype "passive"))
      (node (ref "C26") (pin "2") (pinfunction "2_2") (pintype "passive"))
      (node (ref "C27") (pin "2") (pinfunction "2_2") (pintype "passive"))
      (node (ref "C28") (pin "2") (pinfunction "2_2") (pintype "passive"))
      (node (ref "C29") (pin "2") (pinfunction "2_2") (pintype "passive"))
      (node (ref "C3") (pin "5") (pinfunction "5_5") (pintype "passive"))
      (node (ref "C3") (pin "6") (pinfunction "6_6") (pintype "passive"))
      (node (ref "C3") (pin "7") (pinfunction "7_7") (pintype "passive"))
      (node (ref "C3") (pin "8") (pinfunction "8_8") (pintype "passive"))
      (node (ref "C30") (pin "2") (pinfunction "2_2") (pintype "passive"))
      (node (ref "C31") (pin "2") (pinfunction "2_2") (pintype "passive"))
      (node (ref "C34") (pin "2") (pinfunction "2_2") (pintype "passive"))
      (node (ref "C36") (pin "2") (pinfunction "2_2") (pintype "passive"))
      (node (ref "C37") (pin "2") (pinfunction "2_2") (pintype "passive"))
      (node (ref "C4") (pin "5") (pinfunction "5_5") (pintype "passive"))
      (node (ref "C4") (pin "6") (pinfunction "6_6") (pintype "passive"))
      (node (ref "C4") (pin "7") (pinfunction "7_7") (pintype "passive"))
      (node (ref "C4") (pin "8") (pinfunction "8_8") (pintype "passive"))
      (node (ref "C43") (pin "2") (pinfunction "2_2") (pintype "passive"))
      (node (ref "C44") (pin "2") (pinfunction "2_2") (pintype "passive"))
      (node (ref "C45") (pin "2") (pinfunction "2_2") (pintype "passive"))
      (node (ref "C47") (pin "7") (pinfunction "7_7") (pintype "passive"))
      (node (ref "C47") (pin "8") (pinfunction "8_8") (pintype "passive"))
      (node (ref "C49") (pin "2") (pinfunction "2_2") (pintype "passive"))
      (node (ref "C5") (pin "2") (pinfunction "2_2") (pintype "passive"))
      (node (ref "C50") (pin "2") (pinfunction "2_2") (pintype "passive"))
      (node (ref "C51") (pin "2") (pinfunction "2_2") (pintype "passive"))
      (node (ref "C52") (pin "2") (pinfunction "2_2") (pintype "passive"))
      (node (ref "C53") (pin "2") (pinfunction "2_2") (pintype "passive"))
      (node (ref "C54") (pin "2") (pinfunction "2_2") (pintype "passive"))
      (node (ref "C55") (pin "2") (pinfunction "2_2") (pintype "passive"))
      (node (ref "C56") (pin "2") (pinfunction "2_2") (pintype "passive"))
      (node (ref "C57") (pin "2") (pinfunction "2_2") (pintype "passive"))
      (node (ref "C58") (pin "2") (pinfunction "2_2") (pintype "passive"))
      (node (ref "C59") (pin "1") (pinfunction "1_1") (pintype "passive"))
      (node (ref "C6") (pin "8") (pinfunction "8_8") (pintype "passive"))
      (node (ref "C60") (pin "2") (pinfunction "2_2") (pintype "passive"))
      (node (ref "C8") (pin "2") (pinfunction "2_2") (pintype "passive"))
      (node (ref "LED1") (pin "2") (pinfunction "K_2") (pintype "passive"))
      (node (ref "LED2") (pin "2") (pinfunction "K_2") (pintype "passive"))
      (node (ref "LED3") (pin "2") (pinfunction "K_2") (pintype "passive"))
      (node (ref "P3") (pin "31") (pinfunction "31_31") (pintype "passive"))
      (node (ref "P3") (pin "33") (pinfunction "33_33") (pintype "passive"))
      (node (ref "P3") (pin "41") (pinfunction "41_41") (pintype "passive"))
      (node (ref "P3") (pin "49") (pinfunction "49_49") (pintype "passive"))
      (node (ref "P3") (pin "51") (pinfunction "51_51") (pintype "passive"))
      (node (ref "P3") (pin "52") (pinfunction "52_52") (pintype "passive"))
      (node (ref "P3") (pin "60") (pinfunction "60_60") (pintype "passive"))
      (node (ref "P3") (pin "64") (pinfunction "64_64") (pintype "passive"))
      (node (ref "RPi4") (pin "39") (pinfunction "39_39") (pintype "passive"))
      (node (ref "SV1") (pin "23") (pinfunction "23_23") (pintype "passive"))
      (node (ref "SV1") (pin "24") (pinfunction "24_24") (pintype "passive"))
      (node (ref "U1") (pin "2") (pinfunction "GND_2") (pintype "passive"))
      (node (ref "U10") (pin "2") (pinfunction "GND_2") (pintype "passive"))
      (node (ref "U10") (pin "6") (pinfunction "IO4_6") (pintype "passive"))
      (node (ref "U2") (pin "1") (pinfunction "GND_1") (pintype "passive"))
      (node (ref "U3") (pin "1") (pinfunction "GND_1") (pintype "passive"))
      (node (ref "U4") (pin "2") (pinfunction "GND_2") (pintype "passive"))
      (node (ref "U5") (pin "2") (pinfunction "GND_2") (pintype "passive"))
      (node (ref "U6") (pin "2") (pinfunction "GND_2") (pintype "passive"))
      (node (ref "U7") (pin "2") (pinfunction "GND_2") (pintype "passive"))
      (node (ref "U8") (pin "2") (pinfunction "GND_2") (pintype "passive"))
      (node (ref "U9") (pin "2") (pinfunction "GND_2") (pintype "passive"))
      (node (ref "US1") (pin "31") (pinfunction "RESV1_31") (pintype "passive"))
      (node (ref "US1") (pin "33") (pinfunction "DGND1_33") (pintype "passive"))
      (node (ref "US1") (pin "41") (pinfunction "DAISY_IN_41") (pintype "passive"))
      (node (ref "US1") (pin "49") (pinfunction "DGND2_49") (pintype "passive"))
      (node (ref "US1") (pin "51") (pinfunction "DGND3_51") (pintype "passive"))
      (node (ref "US1") (pin "60") (pinfunction "RLE_REF_60") (pintype "passive"))
      (node (ref "US1") (pin "64") (pinfunction "WCT_64") (pintype "passive"))
    )
    (net (code "68") (name "Net-(LED1-A)") (class "Default")
      (node (ref "LED1") (pin "1") (pinfunction "A_1") (pintype "passive"))
      (node (ref "R23") (pin "1") (pinfunction "1_1") (pintype "passive"))
    )
    (net (code "69") (name "Net-(LED2-A)") (class "Default")
      (node (ref "LED2") (pin "1") (pinfunction "A_1") (pintype "passive"))
      (node (ref "R21") (pin "1") (pinfunction "1_1") (pintype "passive"))
    )
    (net (code "70") (name "Net-(LED3-A)") (class "Default")
      (node (ref "LED3") (pin "1") (pinfunction "A_1") (pintype "passive"))
      (node (ref "R22") (pin "1") (pinfunction "1_1") (pintype "passive"))
    )
    (net (code "71") (name "Net-(U1-NR)") (class "Default")
      (node (ref "C25") (pin "1") (pinfunction "1_1") (pintype "passive"))
      (node (ref "U1") (pin "4") (pinfunction "NR_4") (pintype "passive"))
    )
    (net (code "72") (name "Net-(U2-CAP+)") (class "Default")
      (node (ref "C33") (pin "1") (pinfunction "1_1") (pintype "passive"))
      (node (ref "U2") (pin "6") (pinfunction "CAP+_6") (pintype "passive"))
    )
    (net (code "73") (name "Net-(U2-CAP-)") (class "Default")
      (node (ref "C33") (pin "2") (pinfunction "2_2") (pintype "passive"))
      (node (ref "U2") (pin "3") (pinfunction "CAP-_3") (pintype "passive"))
    )
    (net (code "74") (name "Net-(U3-NR)") (class "Default")
      (node (ref "C28") (pin "1") (pinfunction "1_1") (pintype "passive"))
      (node (ref "U3") (pin "4") (pinfunction "NR_4") (pintype "passive"))
    )
    (net (code "75") (name "Net-(U4-NR{slash}FB)") (class "Default")
      (node (ref "C56") (pin "1") (pinfunction "1_1") (pintype "passive"))
      (node (ref "U4") (pin "4") (pinfunction "NR/FB_4") (pintype "passive"))
    )
    (net (code "76") (name "unconnected-(C6-Pad2)") (class "Default")
      (node (ref "C6") (pin "2") (pinfunction "2_2") (pintype "passive"))
    )
    (net (code "77") (name "unconnected-(C6-Pad3)") (class "Default")
      (node (ref "C6") (pin "3") (pinfunction "3_3") (pintype "passive"))
    )
    (net (code "78") (name "unconnected-(C6-Pad4)") (class "Default")
      (node (ref "C6") (pin "4") (pinfunction "4_4") (pintype "passive"))
    )
    (net (code "79") (name "unconnected-(C6-Pad5)") (class "Default")
      (node (ref "C6") (pin "5") (pinfunction "5_5") (pintype "passive"))
    )
    (net (code "80") (name "unconnected-(C6-Pad6)") (class "Default")
      (node (ref "C6") (pin "6") (pinfunction "6_6") (pintype "passive"))
    )
    (net (code "81") (name "unconnected-(C6-Pad7)") (class "Default")
      (node (ref "C6") (pin "7") (pinfunction "7_7") (pintype "passive"))
    )
    (net (code "82") (name "unconnected-(C47-Pad3)") (class "Default")
      (node (ref "C47") (pin "3") (pinfunction "3_3") (pintype "passive"))
    )
    (net (code "83") (name "unconnected-(C47-Pad4)") (class "Default")
      (node (ref "C47") (pin "4") (pinfunction "4_4") (pintype "passive"))
    )
    (net (code "84") (name "unconnected-(C47-Pad5)") (class "Default")
      (node (ref "C47") (pin "5") (pinfunction "5_5") (pintype "passive"))
    )
    (net (code "85") (name "unconnected-(C47-Pad6)") (class "Default")
      (node (ref "C47") (pin "6") (pinfunction "6_6") (pintype "passive"))
    )
    (net (code "86") (name "unconnected-(R5-Pad3)") (class "Default")
      (node (ref "R5") (pin "3") (pinfunction "3_3") (pintype "passive"))
    )
    (net (code "87") (name "unconnected-(R5-Pad4)") (class "Default")
      (node (ref "R5") (pin "4") (pinfunction "4_4") (pintype "passive"))
    )
    (net (code "88") (name "unconnected-(R5-Pad5)") (class "Default")
      (node (ref "R5") (pin "5") (pinfunction "5_5") (pintype "passive"))
    )
    (net (code "89") (name "unconnected-(R5-Pad6)") (class "Default")
      (node (ref "R5") (pin "6") (pinfunction "6_6") (pintype "passive"))
    )
    (net (code "90") (name "unconnected-(R6-Pad2)") (class "Default")
      (node (ref "R6") (pin "2") (pinfunction "2_2") (pintype "passive"))
    )
    (net (code "91") (name "unconnected-(R6-Pad3)") (class "Default")
      (node (ref "R6") (pin "3") (pinfunction "3_3") (pintype "passive"))
    )
    (net (code "92") (name "unconnected-(R6-Pad4)") (class "Default")
      (node (ref "R6") (pin "4") (pinfunction "4_4") (pintype "passive"))
    )
    (net (code "93") (name "unconnected-(R6-Pad5)") (class "Default")
      (node (ref "R6") (pin "5") (pinfunction "5_5") (pintype "passive"))
    )
    (net (code "94") (name "unconnected-(R6-Pad6)") (class "Default")
      (node (ref "R6") (pin "6") (pinfunction "6_6") (pintype "passive"))
    )
    (net (code "95") (name "unconnected-(R6-Pad7)") (class "Default")
      (node (ref "R6") (pin "7") (pinfunction "7_7") (pintype "passive"))
    )
    (net (code "96") (name "unconnected-(RPi4-Pad1)") (class "Default")
      (node (ref "RPi4") (pin "1") (pinfunction "1_1") (pintype "passive"))
    )
    (net (code "97") (name "unconnected-(RPi4-Pad3)") (class "Default")
      (node (ref "RPi4") (pin "3") (pinfunction "3_3") (pintype "passive"))
    )
    (net (code "98") (name "unconnected-(RPi4-Pad5)") (class "Default")
      (node (ref "RPi4") (pin "5") (pinfunction "5_5") (pintype "passive"))
    )
    (net (code "99") (name "unconnected-(RPi4-Pad6)") (class "Default")
      (node (ref "RPi4") (pin "6") (pinfunction "6_6") (pintype "passive"))
    )
    (net (code "100") (name "unconnected-(RPi4-Pad7)") (class "Default")
      (node (ref "RPi4") (pin "7") (pinfunction "7_7") (pintype "passive"))
    )
    (net (code "101") (name "unconnected-(RPi4-Pad8)") (class "Default")
      (node (ref "RPi4") (pin "8") (pinfunction "8_8") (pintype "passive"))
    )
    (net (code "102") (name "unconnected-(RPi4-Pad9)") (class "Default")
      (node (ref "RPi4") (pin "9") (pinfunction "9_9") (pintype "passive"))
    )
    (net (code "103") (name "unconnected-(RPi4-Pad10)") (class "Default")
      (node (ref "RPi4") (pin "10") (pinfunction "10_10") (pintype "passive"))
    )
    (net (code "104") (name "unconnected-(RPi4-Pad12)") (class "Default")
      (node (ref "RPi4") (pin "12") (pinfunction "12_12") (pintype "passive"))
    )
    (net (code "105") (name "unconnected-(RPi4-Pad14)") (class "Default")
      (node (ref "RPi4") (pin "14") (pinfunction "14_14") (pintype "passive"))
    )
    (net (code "106") (name "unconnected-(RPi4-Pad16)") (class "Default")
      (node (ref "RPi4") (pin "16") (pinfunction "16_16") (pintype "passive"))
    )
    (net (code "107") (name "unconnected-(RPi4-Pad17)") (class "Default")
      (node (ref "RPi4") (pin "17") (pinfunction "17_17") (pintype "passive"))
    )
    (net (code "108") (name "unconnected-(RPi4-Pad18)") (class "Default")
      (node (ref "RPi4") (pin "18") (pinfunction "18_18") (pintype "passive"))
    )
    (net (code "109") (name "unconnected-(RPi4-Pad20)") (class "Default")
      (node (ref "RPi4") (pin "20") (pinfunction "20_20") (pintype "passive"))
    )
    (net (code "110") (name "unconnected-(RPi4-Pad22)") (class "Default")
      (node (ref "RPi4") (pin "22") (pinfunction "22_22") (pintype "passive"))
    )
    (net (code "111") (name "unconnected-(RPi4-Pad25)") (class "Default")
      (node (ref "RPi4") (pin "25") (pinfunction "25_25") (pintype "passive"))
    )
    (net (code "112") (name "unconnected-(RPi4-Pad26)") (class "Default")
      (node (ref "RPi4") (pin "26") (pinfunction "26_26") (pintype "passive"))
    )
    (net (code "113") (name "unconnected-(RPi4-Pad27)") (class "Default")
      (node (ref "RPi4") (pin "27") (pinfunction "27_27") (pintype "passive"))
    )
    (net (code "114") (name "unconnected-(RPi4-Pad28)") (class "Default")
      (node (ref "RPi4") (pin "28") (pinfunction "28_28") (pintype "passive"))
    )
    (net (code "115") (name "unconnected-(RPi4-Pad30)") (class "Default")
      (node (ref "RPi4") (pin "30") (pinfunction "30_30") (pintype "passive"))
    )
    (net (code "116") (name "unconnected-(RPi4-Pad31)") (class "Default")
      (node (ref "RPi4") (pin "31") (pinfunction "31_31") (pintype "passive"))
    )
    (net (code "117") (name "unconnected-(RPi4-Pad32)") (class "Default")
      (node (ref "RPi4") (pin "32") (pinfunction "32_32") (pintype "passive"))
    )
    (net (code "118") (name "unconnected-(RPi4-Pad33)") (class "Default")
      (node (ref "RPi4") (pin "33") (pinfunction "33_33") (pintype "passive"))
    )
    (net (code "119") (name "unconnected-(RPi4-Pad34)") (class "Default")
      (node (ref "RPi4") (pin "34") (pinfunction "34_34") (pintype "passive"))
    )
    (net (code "120") (name "unconnected-(RPi4-Pad35)") (class "Default")
      (node (ref "RPi4") (pin "35") (pinfunction "35_35") (pintype "passive"))
    )
    (net (code "121") (name "unconnected-(RPi4-Pad36)") (class "Default")
      (node (ref "RPi4") (pin "36") (pinfunction "36_36") (pintype "passive"))
    )
    (net (code "122") (name "unconnected-(RPi4-Pad37)") (class "Default")
      (node (ref "RPi4") (pin "37") (pinfunction "37_37") (pintype "passive"))
    )
    (net (code "123") (name "unconnected-(RPi4-Pad38)") (class "Default")
      (node (ref "RPi4") (pin "38") (pinfunction "38_38") (pintype "passive"))
    )
    (net (code "124") (name "unconnected-(RPi4-Pad40)") (class "Default")
      (node (ref "RPi4") (pin "40") (pinfunction "40_40") (pintype "passive"))
    )
    (net (code "125") (name "unconnected-(U9-IO2-Pad3)") (class "Default")
      (node (ref "U9") (pin "3") (pinfunction "IO2_3") (pintype "passive"))
    )
    (net (code "126") (name "unconnected-(U10-IO2-Pad3)") (class "Default")
      (node (ref "U10") (pin "3") (pinfunction "IO2_3") (pintype "passive"))
    )
  )
)
